# ti-tps61288-small-junctions.net
KiCad netlist of a schematic drawn in Altium Designer
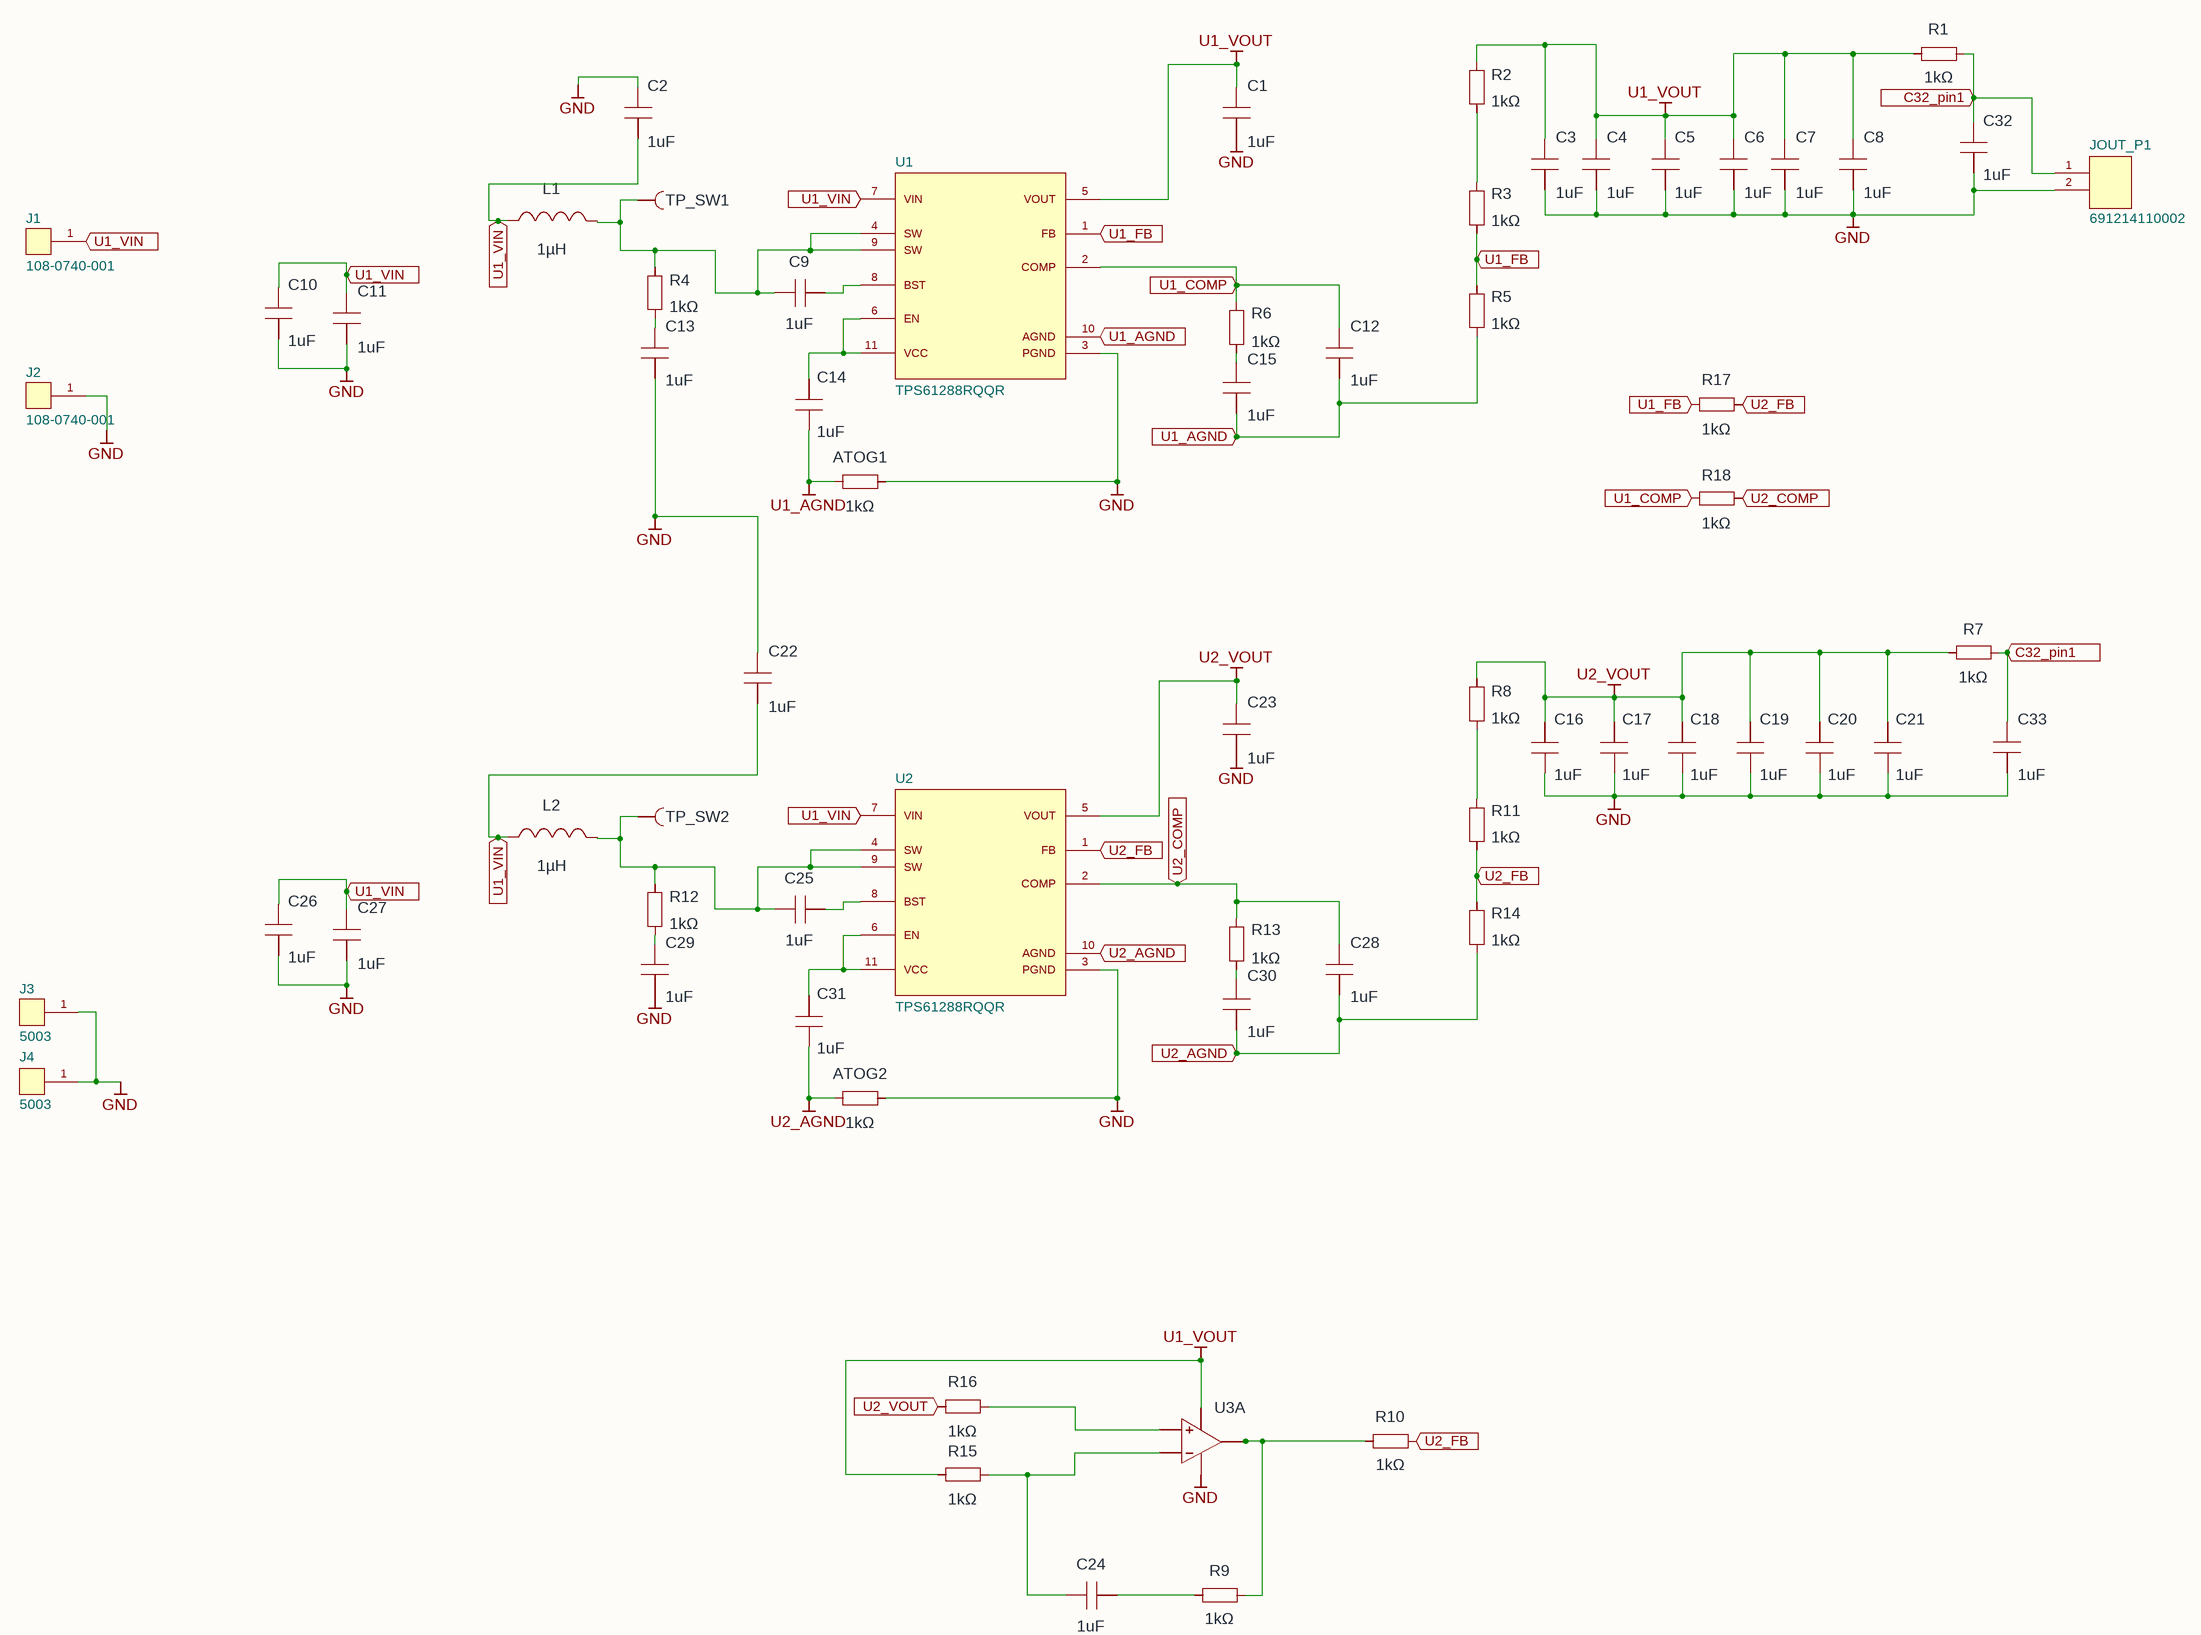
[diagram p0: ti-tps61288-small-junctions.SchDoc]

(export (version "E")
  (design (tool "Eeschema 10.0.6"))
  (components
    (comp (ref "ATOG1") (value "1kΩ") (libsource (lib "altium-import") (part "root_0_boxresistor_left_")))
    (comp (ref "ATOG2") (value "1kΩ") (libsource (lib "altium-import") (part "root_0_boxresistor_left_")))
    (comp (ref "C1") (value "1uF") (libsource (lib "altium-import") (part "root_0_capacitor_down_")))
    (comp (ref "C2") (value "1uF") (libsource (lib "altium-import") (part "root_0_capacitor_down_")))
    (comp (ref "C3") (value "1uF") (libsource (lib "altium-import") (part "root_0_capacitor_down_")))
    (comp (ref "C4") (value "1uF") (libsource (lib "altium-import") (part "root_0_capacitor_down_")))
    (comp (ref "C5") (value "1uF") (libsource (lib "altium-import") (part "root_0_capacitor_down_")))
    (comp (ref "C6") (value "1uF") (libsource (lib "altium-import") (part "root_0_capacitor_down_")))
    (comp (ref "C7") (value "1uF") (libsource (lib "altium-import") (part "root_0_capacitor_down_")))
    (comp (ref "C8") (value "1uF") (libsource (lib "altium-import") (part "root_0_capacitor_down_")))
    (comp (ref "C9") (value "1uF") (libsource (lib "altium-import") (part "root_0_capacitor_right_")))
    (comp (ref "C10") (value "1uF") (libsource (lib "altium-import") (part "root_0_capacitor_down_")))
    (comp (ref "C11") (value "1uF") (libsource (lib "altium-import") (part "root_0_capacitor_down_")))
    (comp (ref "C12") (value "1uF") (libsource (lib "altium-import") (part "root_0_capacitor_down_")))
    (comp (ref "C13") (value "1uF") (libsource (lib "altium-import") (part "root_0_capacitor_down_")))
    (comp (ref "C14") (value "1uF") (libsource (lib "altium-import") (part "root_0_capacitor_up_")))
    (comp (ref "C15") (value "1uF") (libsource (lib "altium-import") (part "root_0_capacitor_down_")))
    (comp (ref "C16") (value "1uF") (libsource (lib "altium-import") (part "root_0_capacitor_up_")))
    (comp (ref "C17") (value "1uF") (libsource (lib "altium-import") (part "root_0_capacitor_up_")))
    (comp (ref "C18") (value "1uF") (libsource (lib "altium-import") (part "root_0_capacitor_up_")))
    (comp (ref "C19") (value "1uF") (libsource (lib "altium-import") (part "root_0_capacitor_up_")))
    (comp (ref "C20") (value "1uF") (libsource (lib "altium-import") (part "root_0_capacitor_up_")))
    (comp (ref "C21") (value "1uF") (libsource (lib "altium-import") (part "root_0_capacitor_up_")))
    (comp (ref "C22") (value "1uF") (libsource (lib "altium-import") (part "root_0_capacitor_down_")))
    (comp (ref "C23") (value "1uF") (libsource (lib "altium-import") (part "root_0_capacitor_down_")))
    (comp (ref "C24") (value "1uF") (libsource (lib "altium-import") (part "root_0_capacitor_left_")))
    (comp (ref "C25") (value "1uF") (libsource (lib "altium-import") (part "root_0_capacitor_right_")))
    (comp (ref "C26") (value "1uF") (libsource (lib "altium-import") (part "root_0_capacitor_down_")))
    (comp (ref "C27") (value "1uF") (libsource (lib "altium-import") (part "root_0_capacitor_down_")))
    (comp (ref "C28") (value "1uF") (libsource (lib "altium-import") (part "root_0_capacitor_down_")))
    (comp (ref "C29") (value "1uF") (libsource (lib "altium-import") (part "root_0_capacitor_down_")))
    (comp (ref "C30") (value "1uF") (libsource (lib "altium-import") (part "root_0_capacitor_down_")))
    (comp (ref "C31") (value "1uF") (libsource (lib "altium-import") (part "root_0_capacitor_up_")))
    (comp (ref "C32") (value "1uF") (libsource (lib "altium-import") (part "root_0_capacitor_down_")))
    (comp (ref "C33") (value "1uF") (libsource (lib "altium-import") (part "root_0_capacitor_down_")))
    (comp (ref "J1") (value "~") (libsource (lib "altium-import") (part "root_0_J1_")))
    (comp (ref "J2") (value "~") (libsource (lib "altium-import") (part "root_0_J2_")))
    (comp (ref "J3") (value "~") (libsource (lib "altium-import") (part "root_0_J3_")))
    (comp (ref "J4") (value "~") (libsource (lib "altium-import") (part "root_0_J4_")))
    (comp (ref "JOUT_P1") (value "~") (libsource (lib "altium-import") (part "root_0_JOUT_P1_")))
    (comp (ref "L1") (value "1µH") (libsource (lib "altium-import") (part "root_0_inductor_right_")))
    (comp (ref "L2") (value "1µH") (libsource (lib "altium-import") (part "root_0_inductor_right_")))
    (comp (ref "R1") (value "1kΩ") (libsource (lib "") (part "root_0_boxresistor_right__1")))
    (comp (ref "R2") (value "1kΩ") (libsource (lib "") (part "root_0_boxresistor_up__1")))
    (comp (ref "R3") (value "1kΩ") (libsource (lib "") (part "root_0_boxresistor_up__2")))
    (comp (ref "R4") (value "1kΩ") (libsource (lib "altium-import") (part "root_0_boxresistor_down_")))
    (comp (ref "R5") (value "1kΩ") (libsource (lib "") (part "root_0_boxresistor_down__1")))
    (comp (ref "R6") (value "1kΩ") (libsource (lib "altium-import") (part "root_0_boxresistor_up_")))
    (comp (ref "R7") (value "1kΩ") (libsource (lib "") (part "root_0_boxresistor_right__2")))
    (comp (ref "R8") (value "1kΩ") (libsource (lib "altium-import") (part "root_0_boxresistor_down_")))
    (comp (ref "R9") (value "1kΩ") (libsource (lib "") (part "root_0_boxresistor_right__1")))
    (comp (ref "R10") (value "1kΩ") (libsource (lib "altium-import") (part "root_0_boxresistor_right_")))
    (comp (ref "R11") (value "1kΩ") (libsource (lib "") (part "root_0_boxresistor_up__2")))
    (comp (ref "R12") (value "1kΩ") (libsource (lib "altium-import") (part "root_0_boxresistor_down_")))
    (comp (ref "R13") (value "1kΩ") (libsource (lib "altium-import") (part "root_0_boxresistor_up_")))
    (comp (ref "R14") (value "1kΩ") (libsource (lib "") (part "root_0_boxresistor_down__1")))
    (comp (ref "R15") (value "1kΩ") (libsource (lib "") (part "root_0_boxresistor_right__1")))
    (comp (ref "R16") (value "1kΩ") (libsource (lib "") (part "root_0_boxresistor_right__1")))
    (comp (ref "R17") (value "1kΩ") (libsource (lib "") (part "root_0_boxresistor_left__1")))
    (comp (ref "R18") (value "1kΩ") (libsource (lib "") (part "root_0_boxresistor_left__1")))
    (comp (ref "TP_SW1") (value "~") (libsource (lib "altium-import") (part "root_0_testpoint_right_")))
    (comp (ref "TP_SW2") (value "~") (libsource (lib "altium-import") (part "root_0_testpoint_right_")))
    (comp (ref "U1") (value "~") (libsource (lib "altium-import") (part "root_0_U1_")))
    (comp (ref "U2") (value "~") (libsource (lib "altium-import") (part "root_0_U2_")))
    (comp (ref "U3A") (value "~") (libsource (lib "altium-import") (part "root_0_opamp_with_power_right_")))
  )
  (nets
    (net (code "1") (name "/C32_pin1") (class "Default")
      (node (ref "C32") (pin "1") (pinfunction "anode_1") (pintype "passive"))
      (node (ref "C33") (pin "1") (pinfunction "anode_1") (pintype "passive"))
      (node (ref "JOUT_P1") (pin "1") (pinfunction "1_1") (pintype "passive"))
      (node (ref "R1") (pin "2") (pinfunction "cathode_2") (pintype "passive"))
      (node (ref "R7") (pin "2") (pinfunction "cathode_2") (pintype "passive"))
    )
    (net (code "2") (name "/U1_COMP") (class "Default")
      (node (ref "C12") (pin "1") (pinfunction "anode_1") (pintype "passive"))
      (node (ref "R18") (pin "2") (pinfunction "cathode_2") (pintype "passive"))
      (node (ref "R6") (pin "2") (pinfunction "cathode_2") (pintype "passive"))
      (node (ref "U1") (pin "2") (pinfunction "COMP_2") (pintype "passive"))
    )
    (net (code "3") (name "/U1_FB") (class "Default")
      (node (ref "R17") (pin "2") (pinfunction "cathode_2") (pintype "passive"))
      (node (ref "R3") (pin "1") (pinfunction "anode_1") (pintype "passive"))
      (node (ref "R5") (pin "1") (pinfunction "anode_1") (pintype "passive"))
      (node (ref "U1") (pin "1") (pinfunction "FB_1") (pintype "passive"))
    )
    (net (code "4") (name "/U1_VIN") (class "Default")
      (node (ref "C10") (pin "1") (pinfunction "anode_1") (pintype "passive"))
      (node (ref "C11") (pin "1") (pinfunction "anode_1") (pintype "passive"))
      (node (ref "C2") (pin "2") (pinfunction "cathode_2") (pintype "passive"))
      (node (ref "C22") (pin "2") (pinfunction "cathode_2") (pintype "passive"))
      (node (ref "C26") (pin "1") (pinfunction "anode_1") (pintype "passive"))
      (node (ref "C27") (pin "1") (pinfunction "anode_1") (pintype "passive"))
      (node (ref "J1") (pin "1") (pinfunction "1_1") (pintype "passive"))
      (node (ref "L1") (pin "1") (pinfunction "anode_1") (pintype "passive"))
      (node (ref "L2") (pin "1") (pinfunction "anode_1") (pintype "passive"))
      (node (ref "U1") (pin "7") (pinfunction "VIN_7") (pintype "passive"))
      (node (ref "U2") (pin "7") (pinfunction "VIN_7") (pintype "passive"))
    )
    (net (code "5") (name "/U2_COMP") (class "Default")
      (node (ref "C28") (pin "1") (pinfunction "anode_1") (pintype "passive"))
      (node (ref "R13") (pin "2") (pinfunction "cathode_2") (pintype "passive"))
      (node (ref "R18") (pin "1") (pinfunction "anode_1") (pintype "passive"))
      (node (ref "U2") (pin "2") (pinfunction "COMP_2") (pintype "passive"))
    )
    (net (code "6") (name "/U2_FB") (class "Default")
      (node (ref "R10") (pin "2") (pinfunction "cathode_2") (pintype "passive"))
      (node (ref "R11") (pin "1") (pinfunction "anode_1") (pintype "passive"))
      (node (ref "R14") (pin "1") (pinfunction "anode_1") (pintype "passive"))
      (node (ref "R17") (pin "1") (pinfunction "anode_1") (pintype "passive"))
      (node (ref "U2") (pin "1") (pinfunction "FB_1") (pintype "passive"))
    )
    (net (code "7") (name "GND") (class "Default")
      (node (ref "ATOG1") (pin "1") (pinfunction "anode_1") (pintype "passive"))
      (node (ref "ATOG2") (pin "1") (pinfunction "anode_1") (pintype "passive"))
      (node (ref "C1") (pin "2") (pinfunction "cathode_2") (pintype "passive"))
      (node (ref "C10") (pin "2") (pinfunction "cathode_2") (pintype "passive"))
      (node (ref "C11") (pin "2") (pinfunction "cathode_2") (pintype "passive"))
      (node (ref "C13") (pin "2") (pinfunction "cathode_2") (pintype "passive"))
      (node (ref "C16") (pin "1") (pinfunction "anode_1") (pintype "passive"))
      (node (ref "C17") (pin "1") (pinfunction "anode_1") (pintype "passive"))
      (node (ref "C18") (pin "1") (pinfunction "anode_1") (pintype "passive"))
      (node (ref "C19") (pin "1") (pinfunction "anode_1") (pintype "passive"))
      (node (ref "C2") (pin "1") (pinfunction "anode_1") (pintype "passive"))
      (node (ref "C20") (pin "1") (pinfunction "anode_1") (pintype "passive"))
      (node (ref "C21") (pin "1") (pinfunction "anode_1") (pintype "passive"))
      (node (ref "C22") (pin "1") (pinfunction "anode_1") (pintype "passive"))
      (node (ref "C23") (pin "2") (pinfunction "cathode_2") (pintype "passive"))
      (node (ref "C26") (pin "2") (pinfunction "cathode_2") (pintype "passive"))
      (node (ref "C27") (pin "2") (pinfunction "cathode_2") (pintype "passive"))
      (node (ref "C29") (pin "2") (pinfunction "cathode_2") (pintype "passive"))
      (node (ref "C3") (pin "2") (pinfunction "cathode_2") (pintype "passive"))
      (node (ref "C32") (pin "2") (pinfunction "cathode_2") (pintype "passive"))
      (node (ref "C33") (pin "2") (pinfunction "cathode_2") (pintype "passive"))
      (node (ref "C4") (pin "2") (pinfunction "cathode_2") (pintype "passive"))
      (node (ref "C5") (pin "2") (pinfunction "cathode_2") (pintype "passive"))
      (node (ref "C6") (pin "2") (pinfunction "cathode_2") (pintype "passive"))
      (node (ref "C7") (pin "2") (pinfunction "cathode_2") (pintype "passive"))
      (node (ref "C8") (pin "2") (pinfunction "cathode_2") (pintype "passive"))
      (node (ref "J2") (pin "1") (pinfunction "1_1") (pintype "passive"))
      (node (ref "J3") (pin "1") (pinfunction "1_1") (pintype "passive"))
      (node (ref "J4") (pin "1") (pinfunction "1_1") (pintype "passive"))
      (node (ref "JOUT_P1") (pin "2") (pinfunction "2_2") (pintype "passive"))
      (node (ref "U1") (pin "3") (pinfunction "PGND_3") (pintype "passive"))
      (node (ref "U2") (pin "3") (pinfunction "PGND_3") (pintype "passive"))
      (node (ref "U3A") (pin "3") (pinfunction "V-_3") (pintype "passive"))
    )
    (net (code "8") (name "Net-(C9-neg)") (class "Default")
      (node (ref "C9") (pin "2") (pinfunction "neg_2") (pintype "passive"))
      (node (ref "U1") (pin "8") (pinfunction "BST_8") (pintype "passive"))
    )
    (net (code "9") (name "Net-(C9-pos)") (class "Default")
      (node (ref "C9") (pin "1") (pinfunction "pos_1") (pintype "passive"))
      (node (ref "L1") (pin "2") (pinfunction "cathode_2") (pintype "passive"))
      (node (ref "R4") (pin "1") (pinfunction "anode_1") (pintype "passive"))
      (node (ref "TP_SW1") (pin "1") (pinfunction "pin1_1") (pintype "passive"))
      (node (ref "U1") (pin "4") (pinfunction "SW_4") (pintype "passive"))
      (node (ref "U1") (pin "9") (pinfunction "SW_9") (pintype "passive"))
    )
    (net (code "10") (name "Net-(C13-anode)") (class "Default")
      (node (ref "C13") (pin "1") (pinfunction "anode_1") (pintype "passive"))
      (node (ref "R4") (pin "2") (pinfunction "cathode_2") (pintype "passive"))
    )
    (net (code "11") (name "Net-(C14-cathode)") (class "Default")
      (node (ref "C14") (pin "2") (pinfunction "cathode_2") (pintype "passive"))
      (node (ref "U1") (pin "11") (pinfunction "VCC_11") (pintype "passive"))
      (node (ref "U1") (pin "6") (pinfunction "EN_6") (pintype "passive"))
    )
    (net (code "12") (name "Net-(C15-anode)") (class "Default")
      (node (ref "C15") (pin "1") (pinfunction "anode_1") (pintype "passive"))
      (node (ref "R6") (pin "1") (pinfunction "anode_1") (pintype "passive"))
    )
    (net (code "13") (name "Net-(C24-neg)") (class "Default")
      (node (ref "C24") (pin "2") (pinfunction "neg_2") (pintype "passive"))
      (node (ref "R15") (pin "2") (pinfunction "cathode_2") (pintype "passive"))
      (node (ref "U3A") (pin "2") (pinfunction "inp2_2") (pintype "passive"))
    )
    (net (code "14") (name "Net-(C24-pos)") (class "Default")
      (node (ref "C24") (pin "1") (pinfunction "pos_1") (pintype "passive"))
      (node (ref "R9") (pin "1") (pinfunction "anode_1") (pintype "passive"))
    )
    (net (code "15") (name "Net-(C25-neg)") (class "Default")
      (node (ref "C25") (pin "2") (pinfunction "neg_2") (pintype "passive"))
      (node (ref "U2") (pin "8") (pinfunction "BST_8") (pintype "passive"))
    )
    (net (code "16") (name "Net-(C25-pos)") (class "Default")
      (node (ref "C25") (pin "1") (pinfunction "pos_1") (pintype "passive"))
      (node (ref "L2") (pin "2") (pinfunction "cathode_2") (pintype "passive"))
      (node (ref "R12") (pin "1") (pinfunction "anode_1") (pintype "passive"))
      (node (ref "TP_SW2") (pin "1") (pinfunction "pin1_1") (pintype "passive"))
      (node (ref "U2") (pin "4") (pinfunction "SW_4") (pintype "passive"))
      (node (ref "U2") (pin "9") (pinfunction "SW_9") (pintype "passive"))
    )
    (net (code "17") (name "Net-(C29-anode)") (class "Default")
      (node (ref "C29") (pin "1") (pinfunction "anode_1") (pintype "passive"))
      (node (ref "R12") (pin "2") (pinfunction "cathode_2") (pintype "passive"))
    )
    (net (code "18") (name "Net-(C30-anode)") (class "Default")
      (node (ref "C30") (pin "1") (pinfunction "anode_1") (pintype "passive"))
      (node (ref "R13") (pin "1") (pinfunction "anode_1") (pintype "passive"))
    )
    (net (code "19") (name "Net-(C31-cathode)") (class "Default")
      (node (ref "C31") (pin "2") (pinfunction "cathode_2") (pintype "passive"))
      (node (ref "U2") (pin "11") (pinfunction "VCC_11") (pintype "passive"))
      (node (ref "U2") (pin "6") (pinfunction "EN_6") (pintype "passive"))
    )
    (net (code "20") (name "Net-(R2-anode)") (class "Default")
      (node (ref "R2") (pin "1") (pinfunction "anode_1") (pintype "passive"))
      (node (ref "R3") (pin "2") (pinfunction "cathode_2") (pintype "passive"))
    )
    (net (code "21") (name "Net-(R10-anode)") (class "Default")
      (node (ref "R10") (pin "1") (pinfunction "anode_1") (pintype "passive"))
      (node (ref "R9") (pin "2") (pinfunction "cathode_2") (pintype "passive"))
      (node (ref "U3A") (pin "4") (pinfunction "out_4") (pintype "passive"))
    )
    (net (code "22") (name "Net-(R11-cathode)") (class "Default")
      (node (ref "R11") (pin "2") (pinfunction "cathode_2") (pintype "passive"))
      (node (ref "R8") (pin "2") (pinfunction "cathode_2") (pintype "passive"))
    )
    (net (code "23") (name "Net-(R16-cathode)") (class "Default")
      (node (ref "R16") (pin "2") (pinfunction "cathode_2") (pintype "passive"))
      (node (ref "U3A") (pin "1") (pinfunction "inp1_1") (pintype "passive"))
    )
    (net (code "24") (name "U1_AGND") (class "Default")
      (node (ref "ATOG1") (pin "2") (pinfunction "cathode_2") (pintype "passive"))
      (node (ref "C12") (pin "2") (pinfunction "cathode_2") (pintype "passive"))
      (node (ref "C14") (pin "1") (pinfunction "anode_1") (pintype "passive"))
      (node (ref "C15") (pin "2") (pinfunction "cathode_2") (pintype "passive"))
      (node (ref "R5") (pin "2") (pinfunction "cathode_2") (pintype "passive"))
      (node (ref "U1") (pin "10") (pinfunction "AGND_10") (pintype "passive"))
    )
    (net (code "25") (name "U1_VOUT") (class "Default")
      (node (ref "C1") (pin "1") (pinfunction "anode_1") (pintype "passive"))
      (node (ref "C3") (pin "1") (pinfunction "anode_1") (pintype "passive"))
      (node (ref "C4") (pin "1") (pinfunction "anode_1") (pintype "passive"))
      (node (ref "C5") (pin "1") (pinfunction "anode_1") (pintype "passive"))
      (node (ref "C6") (pin "1") (pinfunction "anode_1") (pintype "passive"))
      (node (ref "C7") (pin "1") (pinfunction "anode_1") (pintype "passive"))
      (node (ref "C8") (pin "1") (pinfunction "anode_1") (pintype "passive"))
      (node (ref "R1") (pin "1") (pinfunction "anode_1") (pintype "passive"))
      (node (ref "R15") (pin "1") (pinfunction "anode_1") (pintype "passive"))
      (node (ref "R2") (pin "2") (pinfunction "cathode_2") (pintype "passive"))
      (node (ref "U1") (pin "5") (pinfunction "VOUT_5") (pintype "passive"))
      (node (ref "U3A") (pin "5") (pinfunction "V+_5") (pintype "passive"))
    )
    (net (code "26") (name "U2_AGND") (class "Default")
      (node (ref "ATOG2") (pin "2") (pinfunction "cathode_2") (pintype "passive"))
      (node (ref "C28") (pin "2") (pinfunction "cathode_2") (pintype "passive"))
      (node (ref "C30") (pin "2") (pinfunction "cathode_2") (pintype "passive"))
      (node (ref "C31") (pin "1") (pinfunction "anode_1") (pintype "passive"))
      (node (ref "R14") (pin "2") (pinfunction "cathode_2") (pintype "passive"))
      (node (ref "U2") (pin "10") (pinfunction "AGND_10") (pintype "passive"))
    )
    (net (code "27") (name "U2_VOUT") (class "Default")
      (node (ref "C16") (pin "2") (pinfunction "cathode_2") (pintype "passive"))
      (node (ref "C17") (pin "2") (pinfunction "cathode_2") (pintype "passive"))
      (node (ref "C18") (pin "2") (pinfunction "cathode_2") (pintype "passive"))
      (node (ref "C19") (pin "2") (pinfunction "cathode_2") (pintype "passive"))
      (node (ref "C20") (pin "2") (pinfunction "cathode_2") (pintype "passive"))
      (node (ref "C21") (pin "2") (pinfunction "cathode_2") (pintype "passive"))
      (node (ref "C23") (pin "1") (pinfunction "anode_1") (pintype "passive"))
      (node (ref "R16") (pin "1") (pinfunction "anode_1") (pintype "passive"))
      (node (ref "R7") (pin "1") (pinfunction "anode_1") (pintype "passive"))
      (node (ref "R8") (pin "1") (pinfunction "anode_1") (pintype "passive"))
      (node (ref "U2") (pin "5") (pinfunction "VOUT_5") (pintype "passive"))
    )
  )
)
